# tricorder-featherwing-mk-1_2.net
KiCad netlist of a schematic drawn in EAGLE
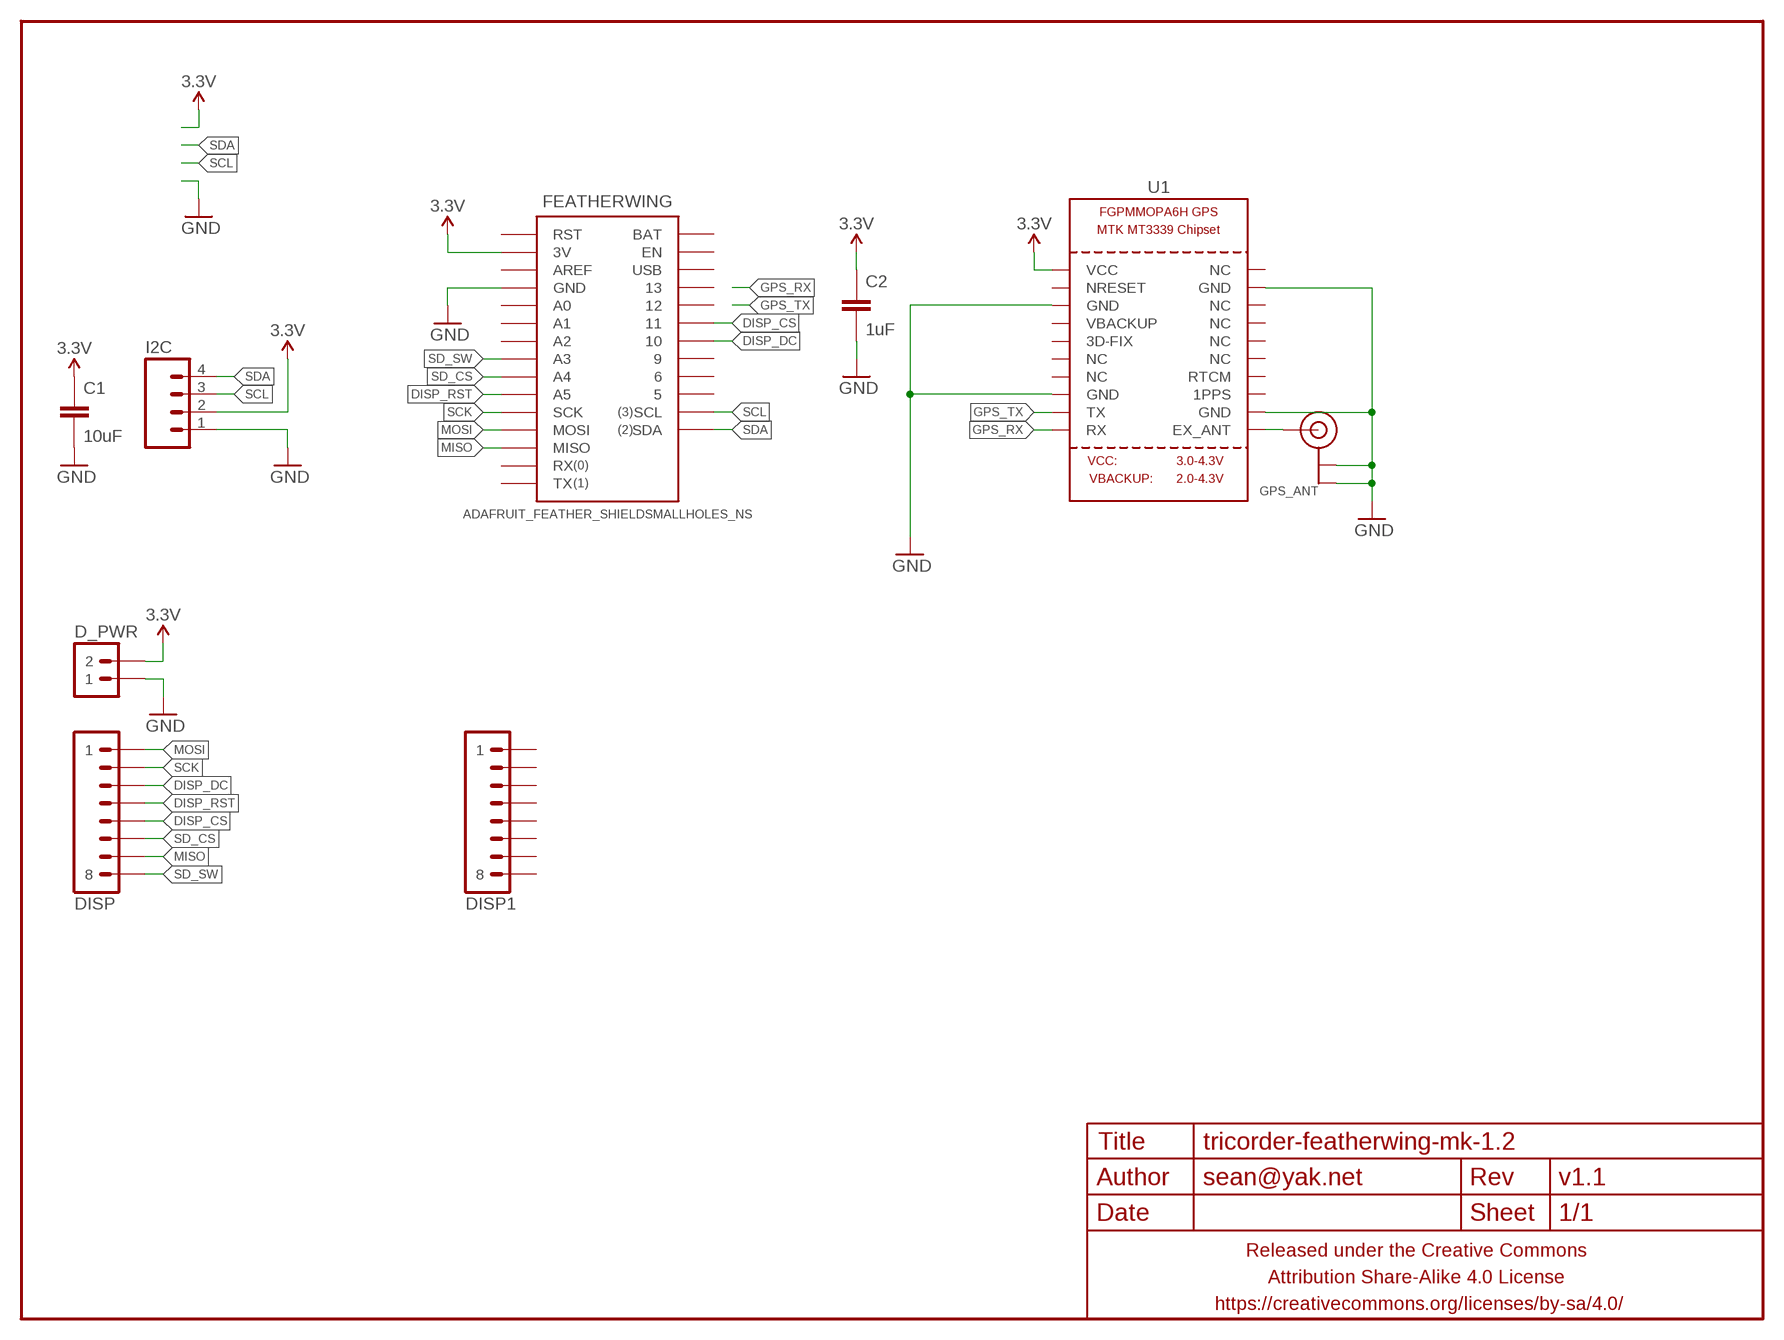
[diagram p0: schematic, sheet 1]

(export (version "E")
  (design (tool "Eeschema 10.0.6"))
  (components
    (comp (ref "C1")
      (value "10uF")
      (footprint "eagle-import:C1210")
      (libsource (lib "eagle-import") (part "CAPACITOR-CERAMICC1210"))
    )
    (comp (ref "C2")
      (value "1uF")
      (footprint "eagle-import:C0603")
      (libsource (lib "eagle-import") (part "CAPACITOR-CERAMICC0603"))
    )
    (comp (ref "DISP")
      (value "M081X08")
      (footprint "eagle-import:1X08")
      (libsource (lib "eagle-import") (part "M081X08"))
    )
    (comp (ref "DISP1")
      (value "M081X08")
      (footprint "eagle-import:1X08")
      (libsource (lib "eagle-import") (part "M081X08"))
    )
    (comp (ref "D_PWR")
      (value "M02PTH")
      (footprint "eagle-import:1X02")
      (libsource (lib "eagle-import") (part "M02PTH"))
    )
    (comp (ref "FEATHERWING")
      (value "ADAFRUIT_FEATHER_SHIELDSMALLHOLES_NS")
      (footprint "eagle-import:ADAFRUIT_FEATHER_SMALLHOLES_NS")
      (libsource (lib "eagle-import") (part "ADAFRUIT_FEATHER_SHIELDSMALLHOLES_NS"))
    )
    (comp (ref "FRAME1")
      (value "FRAME-LETTERNO_PACKAGE")
      (footprint "eagle-import:DUMMY")
      (fields (field (name "DESIGNER") "sean@yak.net") (field (name "VERSION") "v1.1"))
      (libsource (lib "eagle-import") (part "FRAME-LETTERNO_PACKAGE"))
    )
    (comp (ref "GPS_ANT")
      (value "ANTENNA_U.FL")
      (footprint "eagle-import:U.FL")
      (libsource (lib "eagle-import") (part "ANTENNA_U.FL"))
    )
    (comp (ref "I2C")
      (value "M04PTH")
      (footprint "eagle-import:1X04-PTH-VERT")
      (libsource (lib "eagle-import") (part "M04PTH"))
    )
    (comp (ref "U1")
      (value "GPS_FGPMMOPA6H")
      (footprint "eagle-import:FGPMMOPA6H")
      (libsource (lib "eagle-import") (part "GPS_FGPMMOPA6H"))
    )
  )
  (nets
    (net (code "1") (name "3.3V") (class "Default")
      (node (ref "C1") (pin "1") (pinfunction "1_1") (pintype "passive"))
      (node (ref "C2") (pin "1") (pinfunction "1_1") (pintype "passive"))
      (node (ref "D_PWR") (pin "2") (pinfunction "2_2") (pintype "passive"))
      (node (ref "FEATHERWING") (pin "3V") (pinfunction "3V_3V") (pintype "bidirectional"))
      (node (ref "I2C") (pin "2") (pinfunction "2_2") (pintype "passive"))
      (node (ref "U1") (pin "P$1") (pinfunction "VCC_P$1") (pintype "bidirectional"))
    )
    (net (code "2") (name "DISP_CS") (class "Default")
      (node (ref "DISP") (pin "5") (pinfunction "5_5") (pintype "passive"))
      (node (ref "FEATHERWING") (pin "11") (pinfunction "11_11") (pintype "bidirectional"))
    )
    (net (code "3") (name "DISP_DC") (class "Default")
      (node (ref "DISP") (pin "3") (pinfunction "3_3") (pintype "passive"))
      (node (ref "FEATHERWING") (pin "10") (pinfunction "10_10") (pintype "bidirectional"))
    )
    (net (code "4") (name "DISP_RST") (class "Default")
      (node (ref "DISP") (pin "4") (pinfunction "4_4") (pintype "passive"))
      (node (ref "FEATHERWING") (pin "A5") (pinfunction "A5_A5") (pintype "bidirectional"))
    )
    (net (code "5") (name "GND") (class "Default")
      (node (ref "C1") (pin "2") (pinfunction "2_2") (pintype "passive"))
      (node (ref "C2") (pin "2") (pinfunction "2_2") (pintype "passive"))
      (node (ref "D_PWR") (pin "1") (pinfunction "1_1") (pintype "passive"))
      (node (ref "FEATHERWING") (pin "GND@0") (pinfunction "GND_GND@0") (pintype "bidirectional"))
      (node (ref "FEATHERWING") (pin "GND@1") (pinfunction "GND_GND@1") (pintype "bidirectional"))
      (node (ref "GPS_ANT") (pin "1") (pinfunction "GND_1") (pintype "passive"))
      (node (ref "GPS_ANT") (pin "2") (pinfunction "GND_2") (pintype "passive"))
      (node (ref "I2C") (pin "1") (pinfunction "1_1") (pintype "passive"))
      (node (ref "U1") (pin "P$12") (pinfunction "GND_P$12") (pintype "bidirectional"))
      (node (ref "U1") (pin "P$19") (pinfunction "GND_P$19") (pintype "bidirectional"))
      (node (ref "U1") (pin "P$3") (pinfunction "GND_P$3") (pintype "bidirectional"))
      (node (ref "U1") (pin "P$8") (pinfunction "GND_P$8") (pintype "bidirectional"))
    )
    (net (code "6") (name "GPS_RX") (class "Default")
      (node (ref "U1") (pin "P$10") (pinfunction "RX_P$10") (pintype "bidirectional"))
    )
    (net (code "7") (name "GPS_TX") (class "Default")
      (node (ref "U1") (pin "P$9") (pinfunction "TX_P$9") (pintype "bidirectional"))
    )
    (net (code "8") (name "MISO") (class "Default")
      (node (ref "DISP") (pin "7") (pinfunction "7_7") (pintype "passive"))
      (node (ref "FEATHERWING") (pin "MISO") (pinfunction "MISO_MISO") (pintype "bidirectional"))
    )
    (net (code "9") (name "MOSI") (class "Default")
      (node (ref "DISP") (pin "1") (pinfunction "1_1") (pintype "passive"))
      (node (ref "FEATHERWING") (pin "MOSI") (pinfunction "MOSI_MOSI") (pintype "bidirectional"))
    )
    (net (code "10") (name "Net-(GPS_ANT-SIGNAL)") (class "Default")
      (node (ref "GPS_ANT") (pin "3") (pinfunction "SIGNAL_3") (pintype "passive"))
      (node (ref "U1") (pin "P$11") (pinfunction "EX_ANT_P$11") (pintype "bidirectional"))
    )
    (net (code "11") (name "SCK") (class "Default")
      (node (ref "DISP") (pin "2") (pinfunction "2_2") (pintype "passive"))
      (node (ref "FEATHERWING") (pin "SCK") (pinfunction "SCK_SCK") (pintype "bidirectional"))
    )
    (net (code "12") (name "SCL") (class "Default")
      (node (ref "FEATHERWING") (pin "SCL") (pinfunction "SCL_SCL") (pintype "bidirectional"))
      (node (ref "I2C") (pin "3") (pinfunction "3_3") (pintype "passive"))
    )
    (net (code "13") (name "SDA") (class "Default")
      (node (ref "FEATHERWING") (pin "SDA") (pinfunction "SDA_SDA") (pintype "bidirectional"))
      (node (ref "I2C") (pin "4") (pinfunction "4_4") (pintype "passive"))
    )
    (net (code "14") (name "SD_CS") (class "Default")
      (node (ref "DISP") (pin "6") (pinfunction "6_6") (pintype "passive"))
      (node (ref "FEATHERWING") (pin "A4") (pinfunction "A4_A4") (pintype "bidirectional"))
    )
    (net (code "15") (name "SD_SW") (class "Default")
      (node (ref "DISP") (pin "8") (pinfunction "8_8") (pintype "passive"))
      (node (ref "FEATHERWING") (pin "A3") (pinfunction "A3_A3") (pintype "bidirectional"))
    )
    (net (code "16") (name "unconnected-(DISP1-Pad1)") (class "Default")
      (node (ref "DISP1") (pin "1") (pinfunction "1_1") (pintype "passive"))
    )
    (net (code "17") (name "unconnected-(DISP1-Pad2)") (class "Default")
      (node (ref "DISP1") (pin "2") (pinfunction "2_2") (pintype "passive"))
    )
    (net (code "18") (name "unconnected-(DISP1-Pad3)") (class "Default")
      (node (ref "DISP1") (pin "3") (pinfunction "3_3") (pintype "passive"))
    )
    (net (code "19") (name "unconnected-(DISP1-Pad4)") (class "Default")
      (node (ref "DISP1") (pin "4") (pinfunction "4_4") (pintype "passive"))
    )
    (net (code "20") (name "unconnected-(DISP1-Pad5)") (class "Default")
      (node (ref "DISP1") (pin "5") (pinfunction "5_5") (pintype "passive"))
    )
    (net (code "21") (name "unconnected-(DISP1-Pad6)") (class "Default")
      (node (ref "DISP1") (pin "6") (pinfunction "6_6") (pintype "passive"))
    )
    (net (code "22") (name "unconnected-(DISP1-Pad7)") (class "Default")
      (node (ref "DISP1") (pin "7") (pinfunction "7_7") (pintype "passive"))
    )
    (net (code "23") (name "unconnected-(DISP1-Pad8)") (class "Default")
      (node (ref "DISP1") (pin "8") (pinfunction "8_8") (pintype "passive"))
    )
    (net (code "24") (name "unconnected-(FEATHERWING-Pad5)") (class "Default")
      (node (ref "FEATHERWING") (pin "5") (pinfunction "5_5") (pintype "bidirectional"))
    )
    (net (code "25") (name "unconnected-(FEATHERWING-Pad6)") (class "Default")
      (node (ref "FEATHERWING") (pin "6") (pinfunction "6_6") (pintype "bidirectional"))
    )
    (net (code "26") (name "unconnected-(FEATHERWING-Pad9)") (class "Default")
      (node (ref "FEATHERWING") (pin "9") (pinfunction "9_9") (pintype "bidirectional"))
    )
    (net (code "27") (name "unconnected-(FEATHERWING-Pad12)") (class "Default")
      (node (ref "FEATHERWING") (pin "12") (pinfunction "12_12") (pintype "bidirectional"))
    )
    (net (code "28") (name "unconnected-(FEATHERWING-Pad13)") (class "Default")
      (node (ref "FEATHERWING") (pin "13") (pinfunction "13_13") (pintype "bidirectional"))
    )
    (net (code "29") (name "unconnected-(FEATHERWING-PadA0)") (class "Default")
      (node (ref "FEATHERWING") (pin "A0") (pinfunction "A0_A0") (pintype "bidirectional"))
    )
    (net (code "30") (name "unconnected-(FEATHERWING-PadA1)") (class "Default")
      (node (ref "FEATHERWING") (pin "A1") (pinfunction "A1_A1") (pintype "bidirectional"))
    )
    (net (code "31") (name "unconnected-(FEATHERWING-PadA2)") (class "Default")
      (node (ref "FEATHERWING") (pin "A2") (pinfunction "A2_A2") (pintype "bidirectional"))
    )
    (net (code "32") (name "unconnected-(FEATHERWING-PadAREF)") (class "Default")
      (node (ref "FEATHERWING") (pin "AREF") (pinfunction "AREF_AREF") (pintype "bidirectional"))
    )
    (net (code "33") (name "unconnected-(FEATHERWING-PadBAT)") (class "Default")
      (node (ref "FEATHERWING") (pin "BAT") (pinfunction "BAT_BAT") (pintype "bidirectional"))
    )
    (net (code "34") (name "unconnected-(FEATHERWING-PadEN)") (class "Default")
      (node (ref "FEATHERWING") (pin "EN") (pinfunction "EN_EN") (pintype "bidirectional"))
    )
    (net (code "35") (name "unconnected-(FEATHERWING-PadRST)") (class "Default")
      (node (ref "FEATHERWING") (pin "RST") (pinfunction "RST_RST") (pintype "bidirectional"))
    )
    (net (code "36") (name "unconnected-(FEATHERWING-PadRX)") (class "Default")
      (node (ref "FEATHERWING") (pin "RX") (pinfunction "RX_RX") (pintype "bidirectional"))
    )
    (net (code "37") (name "unconnected-(FEATHERWING-PadTX)") (class "Default")
      (node (ref "FEATHERWING") (pin "TX") (pinfunction "TX_TX") (pintype "bidirectional"))
    )
    (net (code "38") (name "unconnected-(FEATHERWING-PadUSB)") (class "Default")
      (node (ref "FEATHERWING") (pin "USB") (pinfunction "USB_USB") (pintype "bidirectional"))
    )
    (net (code "39") (name "unconnected-(U1-1PPS-PadP$13)") (class "Default")
      (node (ref "U1") (pin "P$13") (pinfunction "1PPS_P$13") (pintype "bidirectional"))
    )
    (net (code "40") (name "unconnected-(U1-3D-FIX-PadP$5)") (class "Default")
      (node (ref "U1") (pin "P$5") (pinfunction "3D-FIX_P$5") (pintype "bidirectional"))
    )
    (net (code "41") (name "unconnected-(U1-NC-PadP$6)") (class "Default")
      (node (ref "U1") (pin "P$6") (pinfunction "NC_P$6") (pintype "bidirectional"))
    )
    (net (code "42") (name "unconnected-(U1-NC-PadP$7)") (class "Default")
      (node (ref "U1") (pin "P$7") (pinfunction "NC_P$7") (pintype "bidirectional"))
    )
    (net (code "43") (name "unconnected-(U1-NC-PadP$15)") (class "Default")
      (node (ref "U1") (pin "P$15") (pinfunction "NC_P$15") (pintype "bidirectional"))
    )
    (net (code "44") (name "unconnected-(U1-NC-PadP$16)") (class "Default")
      (node (ref "U1") (pin "P$16") (pinfunction "NC_P$16") (pintype "bidirectional"))
    )
    (net (code "45") (name "unconnected-(U1-NC-PadP$17)") (class "Default")
      (node (ref "U1") (pin "P$17") (pinfunction "NC_P$17") (pintype "bidirectional"))
    )
    (net (code "46") (name "unconnected-(U1-NC-PadP$18)") (class "Default")
      (node (ref "U1") (pin "P$18") (pinfunction "NC_P$18") (pintype "bidirectional"))
    )
    (net (code "47") (name "unconnected-(U1-NC-PadP$20)") (class "Default")
      (node (ref "U1") (pin "P$20") (pinfunction "NC_P$20") (pintype "bidirectional"))
    )
    (net (code "48") (name "unconnected-(U1-NRESET-PadP$2)") (class "Default")
      (node (ref "U1") (pin "P$2") (pinfunction "NRESET_P$2") (pintype "bidirectional"))
    )
    (net (code "49") (name "unconnected-(U1-RTCM-PadP$14)") (class "Default")
      (node (ref "U1") (pin "P$14") (pinfunction "RTCM_P$14") (pintype "bidirectional"))
    )
    (net (code "50") (name "unconnected-(U1-VBACKUP-PadP$4)") (class "Default")
      (node (ref "U1") (pin "P$4") (pinfunction "VBACKUP_P$4") (pintype "bidirectional"))
    )
  )
)
